# Power_Supply.net
KiCad netlist of a schematic drawn in Altium Designer
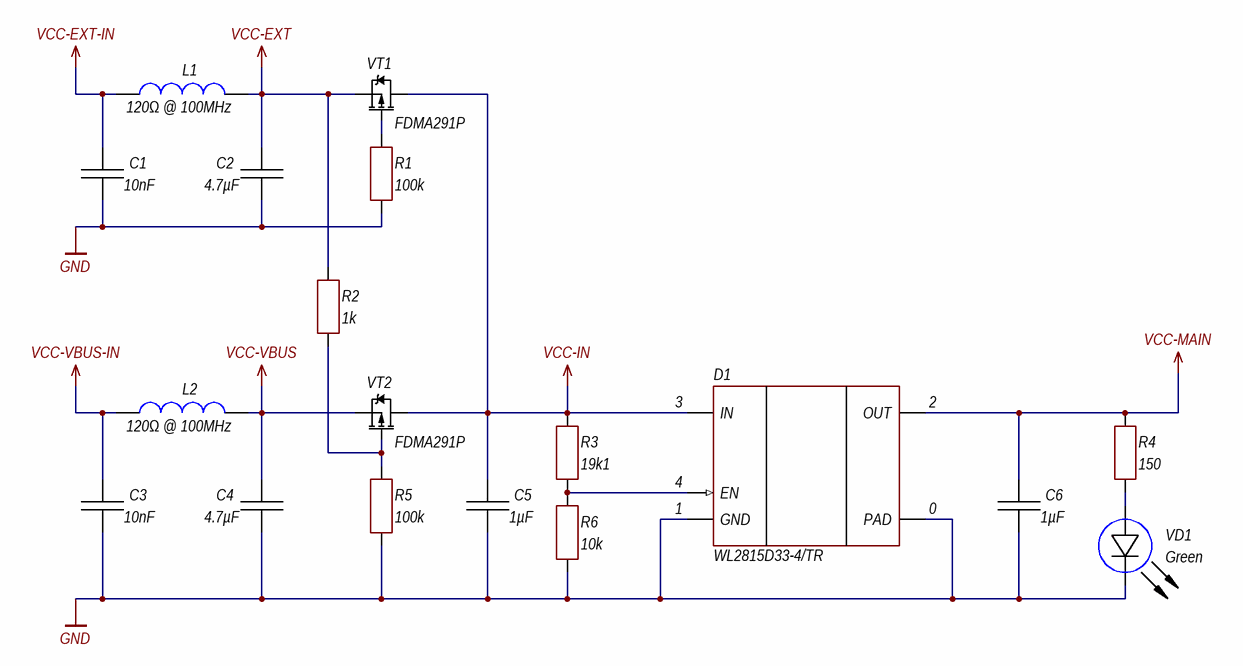
[diagram p0: Power Supply.SchDoc]

(export (version "E")
  (design (tool "Eeschema 10.0.6"))
  (components
    (comp (ref "C1") (value "10nF") (footprint "CH0805CM") (libsource (lib "Discrete") (part "Capacitor")))
    (comp (ref "C2") (value "4.7µF") (footprint "CH0805CM") (libsource (lib "Discrete") (part "Capacitor")))
    (comp (ref "C3") (value "10nF") (footprint "CH0805CM") (libsource (lib "Discrete") (part "Capacitor")))
    (comp (ref "C4") (value "4.7µF") (footprint "CH0805CM") (libsource (lib "Discrete") (part "Capacitor")))
    (comp (ref "C5") (value "1µF") (footprint "CH0402C") (libsource (lib "Discrete") (part "Capacitor")))
    (comp (ref "C6") (value "1µF") (footprint "CH0402C") (libsource (lib "Discrete") (part "Capacitor")))
    (comp (ref "D1")
      (value "WL2815D33-4/TR")
      (footprint "DFN1010-4")
      (description "LDO")
      (libsource (lib "Power Supplies") (part "WL2815"))
    )
    (comp (ref "L1")
      (value "120Ω @ 100MHz")
      (footprint "CH0805LM")
      (libsource (lib "Discrete") (part "Inductor"))
    )
    (comp (ref "L2")
      (value "120Ω @ 100MHz")
      (footprint "CH0805LM")
      (libsource (lib "Discrete") (part "Inductor"))
    )
    (comp (ref "R1") (value "100k") (footprint "CH0402R") (libsource (lib "Discrete") (part "Resistor")))
    (comp (ref "R2") (value "1k") (footprint "CH0402R") (libsource (lib "Discrete") (part "Resistor")))
    (comp (ref "R3") (value "19k1") (footprint "CH0402R") (libsource (lib "Discrete") (part "Resistor")))
    (comp (ref "R4") (value "150") (footprint "CH0402R") (libsource (lib "Discrete") (part "Resistor")))
    (comp (ref "R5") (value "100k") (footprint "CH0402R") (libsource (lib "Discrete") (part "Resistor")))
    (comp (ref "R6") (value "10k") (footprint "CH0402R") (libsource (lib "Discrete") (part "Resistor")))
    (comp (ref "VD1") (value "Green") (footprint "CH0402LG") (libsource (lib "Discrete") (part "LED")))
    (comp (ref "VT1")
      (value "FDMA291P")
      (footprint "MicroFET 2x2")
      (description "Mosfet")
      (fields (field (name "MANUFACTURER") "Fairchild Semiconductor"))
      (libsource (lib "Transistor") (part "P-chanel"))
    )
    (comp (ref "VT2")
      (value "FDMA291P")
      (footprint "MicroFET 2x2")
      (description "Mosfet")
      (fields (field (name "MANUFACTURER") "Fairchild Semiconductor"))
      (libsource (lib "Transistor") (part "P-chanel"))
    )
  )
  (nets
    (net (code "1") (name "GND") (class "Default")
      (node (ref "C1") (pin "1") (pinfunction "1_1") (pintype "passive"))
      (node (ref "C2") (pin "1") (pinfunction "1_1") (pintype "passive"))
      (node (ref "C3") (pin "1") (pinfunction "1_1") (pintype "passive"))
      (node (ref "C4") (pin "1") (pinfunction "1_1") (pintype "passive"))
      (node (ref "C5") (pin "1") (pinfunction "1_1") (pintype "passive"))
      (node (ref "C6") (pin "1") (pinfunction "1_1") (pintype "passive"))
      (node (ref "D1") (pin "0") (pinfunction "PAD_0") (pintype "power_in"))
      (node (ref "D1") (pin "1") (pinfunction "GND_1") (pintype "power_in"))
      (node (ref "R1") (pin "1") (pinfunction "1_1") (pintype "passive"))
      (node (ref "R5") (pin "1") (pinfunction "1_1") (pintype "passive"))
      (node (ref "R6") (pin "1") (pinfunction "1_1") (pintype "passive"))
      (node (ref "VD1") (pin "2") (pinfunction "C_2") (pintype "passive"))
    )
    (net (code "2") (name "Net-(D1-EN)") (class "Default")
      (node (ref "D1") (pin "4") (pinfunction "EN_4") (pintype "input"))
      (node (ref "R3") (pin "1") (pinfunction "1_1") (pintype "passive"))
      (node (ref "R6") (pin "2") (pinfunction "2_2") (pintype "passive"))
    )
    (net (code "3") (name "Net-(VD1-A)") (class "Default")
      (node (ref "R4") (pin "1") (pinfunction "1_1") (pintype "passive"))
      (node (ref "VD1") (pin "1") (pinfunction "A_1") (pintype "passive"))
    )
    (net (code "4") (name "Net-(VT1-G)") (class "Default")
      (node (ref "R1") (pin "2") (pinfunction "2_2") (pintype "passive"))
      (node (ref "VT1") (pin "1") (pinfunction "G_1") (pintype "passive"))
    )
    (net (code "5") (name "Net-(VT2-G)") (class "Default")
      (node (ref "R2") (pin "1") (pinfunction "1_1") (pintype "passive"))
      (node (ref "R5") (pin "2") (pinfunction "2_2") (pintype "passive"))
      (node (ref "VT2") (pin "1") (pinfunction "G_1") (pintype "passive"))
    )
    (net (code "6") (name "VCC-EXT") (class "Default")
      (node (ref "C2") (pin "2") (pinfunction "2_2") (pintype "passive"))
      (node (ref "L1") (pin "1") (pinfunction "1_1") (pintype "passive"))
      (node (ref "R2") (pin "2") (pinfunction "2_2") (pintype "passive"))
      (node (ref "VT1") (pin "3") (pinfunction "S_3") (pintype "passive"))
    )
    (net (code "7") (name "VCC-EXT-IN") (class "Default")
      (node (ref "C1") (pin "2") (pinfunction "2_2") (pintype "passive"))
      (node (ref "L1") (pin "2") (pinfunction "2_2") (pintype "passive"))
    )
    (net (code "8") (name "VCC-IN") (class "Default")
      (node (ref "C5") (pin "2") (pinfunction "2_2") (pintype "passive"))
      (node (ref "D1") (pin "3") (pinfunction "IN_3") (pintype "power_in"))
      (node (ref "R3") (pin "2") (pinfunction "2_2") (pintype "passive"))
      (node (ref "VT1") (pin "2") (pinfunction "D_2") (pintype "passive"))
      (node (ref "VT2") (pin "2") (pinfunction "D_2") (pintype "passive"))
    )
    (net (code "9") (name "VCC-MAIN") (class "Default")
      (node (ref "C6") (pin "2") (pinfunction "2_2") (pintype "passive"))
      (node (ref "D1") (pin "2") (pinfunction "OUT_2") (pintype "power_in"))
      (node (ref "R4") (pin "2") (pinfunction "2_2") (pintype "passive"))
    )
    (net (code "10") (name "VCC-VBUS") (class "Default")
      (node (ref "C4") (pin "2") (pinfunction "2_2") (pintype "passive"))
      (node (ref "L2") (pin "1") (pinfunction "1_1") (pintype "passive"))
      (node (ref "VT2") (pin "3") (pinfunction "S_3") (pintype "passive"))
    )
    (net (code "11") (name "VCC-VBUS-IN") (class "Default")
      (node (ref "C3") (pin "2") (pinfunction "2_2") (pintype "passive"))
      (node (ref "L2") (pin "2") (pinfunction "2_2") (pintype "passive"))
    )
  )
)
